# eagle.net
KiCad netlist of a schematic drawn in EAGLE
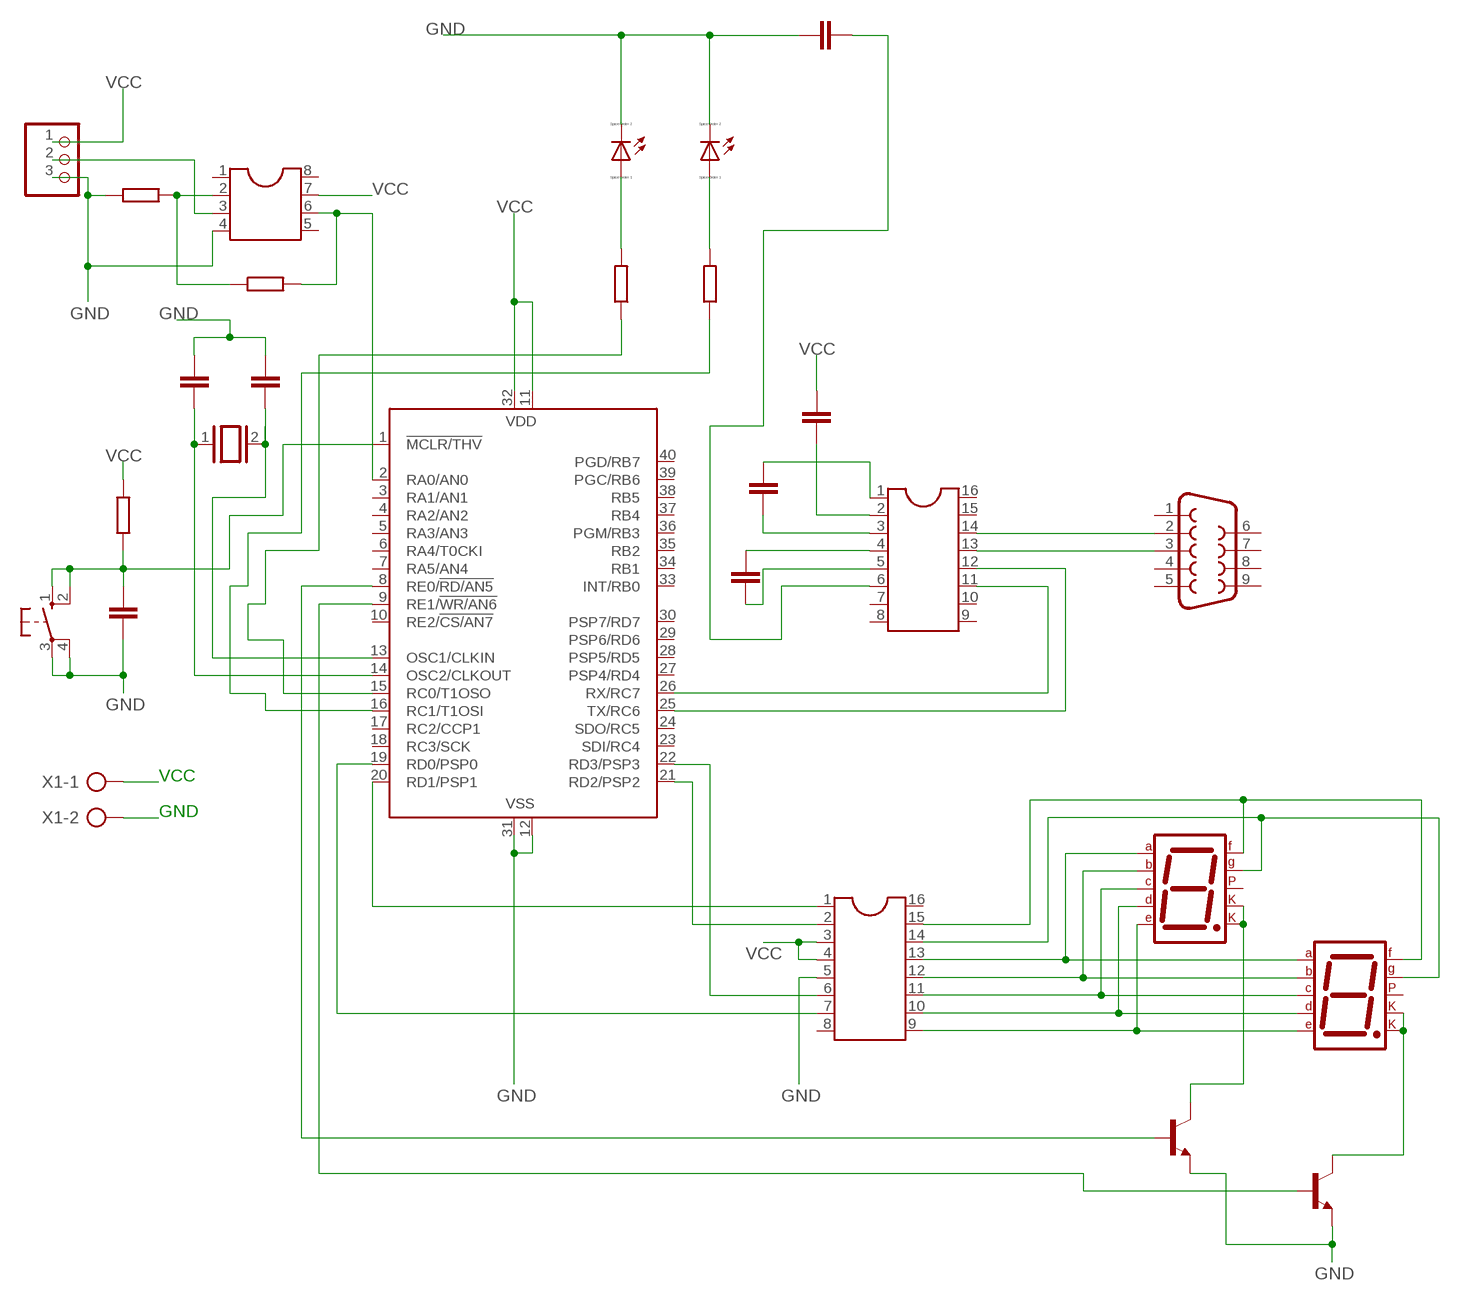
[diagram p0: schematic, sheet 1]

(export (version "E")
  (design (tool "Eeschema 10.0.6"))
  (components
    (comp (ref "4511")
      (value "DIL16")
      (footprint "eagle-import:DIL16")
      (libsource (lib "eagle-import") (part "DIL16"))
    )
    (comp (ref "AMPLIOP")
      (value "DIL8")
      (footprint "eagle-import:DIL08")
      (libsource (lib "eagle-import") (part "DIL8"))
    )
    (comp (ref "C1")
      (value "15pF")
      (footprint "eagle-import:C025-050X050")
      (libsource (lib "eagle-import") (part "C-EU025-050X050"))
    )
    (comp (ref "C2")
      (value "15pF")
      (footprint "eagle-import:C025-050X050")
      (libsource (lib "eagle-import") (part "C-EU025-050X050"))
    )
    (comp (ref "C3")
      (value "1uF")
      (footprint "eagle-import:C025-050X050")
      (libsource (lib "eagle-import") (part "C-EU025-050X050"))
    )
    (comp (ref "C4")
      (value "10uF")
      (footprint "eagle-import:C025-050X050")
      (libsource (lib "eagle-import") (part "C-EU025-050X050"))
    )
    (comp (ref "C5")
      (value "10uF")
      (footprint "eagle-import:C025-050X050")
      (libsource (lib "eagle-import") (part "C-EU025-050X050"))
    )
    (comp (ref "C7")
      (value "100u")
      (footprint "eagle-import:C025-050X050")
      (libsource (lib "eagle-import") (part "C-EU025-050X050"))
    )
    (comp (ref "C61")
      (value "10uF")
      (footprint "eagle-import:C025-050X050")
      (libsource (lib "eagle-import") (part "C-EU025-050X050"))
    )
    (comp (ref "D1")
      (value "7SEG-CK")
      (footprint "eagle-import:7SEG-13")
      (libsource (lib "eagle-import") (part "7SEG-CK"))
    )
    (comp (ref "D2")
      (value "7SEG-CK")
      (footprint "eagle-import:7SEG-13")
      (libsource (lib "eagle-import") (part "7SEG-CK"))
    )
    (comp (ref "LED1")
      (value "LED_ELD260")
      (footprint "eagle-import:LED_LD260")
      (libsource (lib "eagle-import") (part "LED_ELD260"))
    )
    (comp (ref "LED2")
      (value "LED_ELD260")
      (footprint "eagle-import:LED_LD260")
      (libsource (lib "eagle-import") (part "LED_ELD260"))
    )
    (comp (ref "LM35")
      (value "PINHD-1X3")
      (footprint "eagle-import:1X03")
      (libsource (lib "eagle-import") (part "PINHD-1X3"))
    )
    (comp (ref "MAX232")
      (value "DIL16")
      (footprint "eagle-import:DIL16")
      (libsource (lib "eagle-import") (part "DIL16"))
    )
    (comp (ref "P1/COMPIM")
      (value "F09V")
      (footprint "eagle-import:F09V")
      (libsource (lib "eagle-import") (part "F09V"))
    )
    (comp (ref "Q1")
      (value "2N2222")
      (footprint "eagle-import:TO18")
      (libsource (lib "eagle-import") (part "2N2222"))
    )
    (comp (ref "Q2")
      (value "2N2222")
      (footprint "eagle-import:TO18")
      (libsource (lib "eagle-import") (part "2N2222"))
    )
    (comp (ref "R1")
      (value "10k")
      (footprint "eagle-import:0204_7")
      (libsource (lib "eagle-import") (part "R-EU_0204/7"))
    )
    (comp (ref "R2")
      (value "100")
      (footprint "eagle-import:0204_7")
      (libsource (lib "eagle-import") (part "R-EU_0204/7"))
    )
    (comp (ref "R3")
      (value "1k")
      (footprint "eagle-import:0204_7")
      (libsource (lib "eagle-import") (part "R-EU_0204/7"))
    )
    (comp (ref "R4")
      (value "280")
      (footprint "eagle-import:0204_7")
      (libsource (lib "eagle-import") (part "R-EU_0204/7"))
    )
    (comp (ref "R5")
      (value "280")
      (footprint "eagle-import:0204_7")
      (libsource (lib "eagle-import") (part "R-EU_0204/7"))
    )
    (comp (ref "S1")
      (value "10-XX")
      (footprint "eagle-import:B3F-10XX")
      (fields (field (name "MPN") "B3F-1000"))
      (libsource (lib "eagle-import") (part "10-XX"))
    )
    (comp (ref "U1")
      (value "PIC16F877P")
      (footprint "eagle-import:DIL40")
      (fields (field (name "MF") "MICROCHIP") (field (name "MPN") "PIC16F877-04/P"))
      (libsource (lib "eagle-import") (part "PIC16F87P7"))
    )
    (comp (ref "X1")
      (value "AK300/2")
      (footprint "eagle-import:AK300_2")
      (libsource (lib "eagle-import") (part "AK300/2"))
    )
    (comp (ref "X11")
      (value "XTAL/S")
      (footprint "eagle-import:QS")
      (libsource (lib "eagle-import") (part "XTAL/S"))
    )
  )
  (nets
    (net (code "1") (name "/GND") (class "Default")
      (node (ref "4511") (pin "5") (pinfunction "5_5") (pintype "passive"))
      (node (ref "AMPLIOP") (pin "4") (pinfunction "4_4") (pintype "passive"))
      (node (ref "C1") (pin "1") (pinfunction "1_1") (pintype "passive"))
      (node (ref "C2") (pin "1") (pinfunction "1_1") (pintype "passive"))
      (node (ref "C3") (pin "1") (pinfunction "1_1") (pintype "passive"))
      (node (ref "C61") (pin "2") (pinfunction "2_2") (pintype "passive"))
      (node (ref "LED1") (pin "K") (pinfunction "C_K") (pintype "passive"))
      (node (ref "LED2") (pin "K") (pinfunction "C_K") (pintype "passive"))
      (node (ref "LM35") (pin "3") (pinfunction "3_3") (pintype "passive"))
      (node (ref "Q1") (pin "1") (pinfunction "E_1") (pintype "passive"))
      (node (ref "Q2") (pin "1") (pinfunction "E_1") (pintype "passive"))
      (node (ref "R2") (pin "1") (pinfunction "1_1") (pintype "passive"))
      (node (ref "S1") (pin "3") (pinfunction "P_3") (pintype "passive"))
      (node (ref "S1") (pin "4") (pinfunction "P1_4") (pintype "passive"))
      (node (ref "U1") (pin "12") (pinfunction "VSS_12") (pintype "power_in"))
      (node (ref "U1") (pin "31") (pinfunction "VSS_31") (pintype "power_in"))
      (node (ref "X1") (pin "2") (pinfunction "KL_2") (pintype "passive"))
    )
    (net (code "2") (name "/VCC") (class "Default")
      (node (ref "4511") (pin "3") (pinfunction "3_3") (pintype "passive"))
      (node (ref "4511") (pin "4") (pinfunction "4_4") (pintype "passive"))
      (node (ref "AMPLIOP") (pin "7") (pinfunction "7_7") (pintype "passive"))
      (node (ref "C7") (pin "2") (pinfunction "2_2") (pintype "passive"))
      (node (ref "LM35") (pin "1") (pinfunction "1_1") (pintype "passive"))
      (node (ref "R1") (pin "2") (pinfunction "2_2") (pintype "passive"))
      (node (ref "U1") (pin "11") (pinfunction "VDD_11") (pintype "power_in"))
      (node (ref "U1") (pin "32") (pinfunction "VDD_32") (pintype "power_in"))
      (node (ref "X1") (pin "1") (pinfunction "KL_1") (pintype "passive"))
    )
    (net (code "3") (name "Net-(AMPLIOP-Pad2)") (class "Default")
      (node (ref "AMPLIOP") (pin "2") (pinfunction "2_2") (pintype "passive"))
      (node (ref "R2") (pin "2") (pinfunction "2_2") (pintype "passive"))
      (node (ref "R3") (pin "1") (pinfunction "1_1") (pintype "passive"))
    )
    (net (code "4") (name "Net-(AMPLIOP-Pad3)") (class "Default")
      (node (ref "AMPLIOP") (pin "3") (pinfunction "3_3") (pintype "passive"))
      (node (ref "LM35") (pin "2") (pinfunction "2_2") (pintype "passive"))
    )
    (net (code "5") (name "Net-(C4-Pad1)") (class "Default")
      (node (ref "C4") (pin "1") (pinfunction "1_1") (pintype "passive"))
      (node (ref "MAX232") (pin "3") (pinfunction "3_3") (pintype "passive"))
    )
    (net (code "6") (name "Net-(C4-Pad2)") (class "Default")
      (node (ref "C4") (pin "2") (pinfunction "2_2") (pintype "passive"))
      (node (ref "MAX232") (pin "1") (pinfunction "1_1") (pintype "passive"))
    )
    (net (code "7") (name "Net-(C5-Pad1)") (class "Default")
      (node (ref "C5") (pin "1") (pinfunction "1_1") (pintype "passive"))
      (node (ref "MAX232") (pin "5") (pinfunction "5_5") (pintype "passive"))
    )
    (net (code "8") (name "Net-(C5-Pad2)") (class "Default")
      (node (ref "C5") (pin "2") (pinfunction "2_2") (pintype "passive"))
      (node (ref "MAX232") (pin "4") (pinfunction "4_4") (pintype "passive"))
    )
    (net (code "9") (name "Net-(C7-Pad1)") (class "Default")
      (node (ref "C7") (pin "1") (pinfunction "1_1") (pintype "passive"))
      (node (ref "MAX232") (pin "2") (pinfunction "2_2") (pintype "passive"))
    )
    (net (code "10") (name "Net-(C61-Pad1)") (class "Default")
      (node (ref "C61") (pin "1") (pinfunction "1_1") (pintype "passive"))
      (node (ref "MAX232") (pin "6") (pinfunction "6_6") (pintype "passive"))
    )
    (net (code "11") (name "Net-(D1-A)") (class "Default")
      (node (ref "4511") (pin "13") (pinfunction "13_13") (pintype "passive"))
      (node (ref "D1") (pin "7") (pinfunction "A_7") (pintype "passive"))
      (node (ref "D2") (pin "7") (pinfunction "A_7") (pintype "passive"))
    )
    (net (code "12") (name "Net-(D1-B)") (class "Default")
      (node (ref "4511") (pin "12") (pinfunction "12_12") (pintype "passive"))
      (node (ref "D1") (pin "6") (pinfunction "B_6") (pintype "passive"))
      (node (ref "D2") (pin "6") (pinfunction "B_6") (pintype "passive"))
    )
    (net (code "13") (name "Net-(D1-C)") (class "Default")
      (node (ref "4511") (pin "11") (pinfunction "11_11") (pintype "passive"))
      (node (ref "D1") (pin "4") (pinfunction "C_4") (pintype "passive"))
      (node (ref "D2") (pin "4") (pinfunction "C_4") (pintype "passive"))
    )
    (net (code "14") (name "Net-(D1-CK1)") (class "Default")
      (node (ref "D1") (pin "3") (pinfunction "CK1_3") (pintype "passive"))
      (node (ref "D1") (pin "8") (pinfunction "CK2_8") (pintype "passive"))
      (node (ref "Q1") (pin "3") (pinfunction "C_3") (pintype "passive"))
    )
    (net (code "15") (name "Net-(D1-D)") (class "Default")
      (node (ref "4511") (pin "10") (pinfunction "10_10") (pintype "passive"))
      (node (ref "D1") (pin "2") (pinfunction "D_2") (pintype "passive"))
      (node (ref "D2") (pin "2") (pinfunction "D_2") (pintype "passive"))
    )
    (net (code "16") (name "Net-(D1-E)") (class "Default")
      (node (ref "4511") (pin "9") (pinfunction "9_9") (pintype "passive"))
      (node (ref "D1") (pin "1") (pinfunction "E_1") (pintype "passive"))
      (node (ref "D2") (pin "1") (pinfunction "E_1") (pintype "passive"))
    )
    (net (code "17") (name "Net-(D1-F)") (class "Default")
      (node (ref "4511") (pin "15") (pinfunction "15_15") (pintype "passive"))
      (node (ref "D1") (pin "9") (pinfunction "F_9") (pintype "passive"))
      (node (ref "D2") (pin "9") (pinfunction "F_9") (pintype "passive"))
    )
    (net (code "18") (name "Net-(D1-G)") (class "Default")
      (node (ref "4511") (pin "14") (pinfunction "14_14") (pintype "passive"))
      (node (ref "D1") (pin "10") (pinfunction "G_10") (pintype "passive"))
      (node (ref "D2") (pin "10") (pinfunction "G_10") (pintype "passive"))
    )
    (net (code "19") (name "Net-(D2-CK1)") (class "Default")
      (node (ref "D2") (pin "3") (pinfunction "CK1_3") (pintype "passive"))
      (node (ref "D2") (pin "8") (pinfunction "CK2_8") (pintype "passive"))
      (node (ref "Q2") (pin "3") (pinfunction "C_3") (pintype "passive"))
    )
    (net (code "20") (name "Net-(LED1-PadA)") (class "Default")
      (node (ref "LED1") (pin "A") (pinfunction "A_A") (pintype "passive"))
      (node (ref "R4") (pin "2") (pinfunction "2_2") (pintype "passive"))
    )
    (net (code "21") (name "Net-(LED2-PadA)") (class "Default")
      (node (ref "LED2") (pin "A") (pinfunction "A_A") (pintype "passive"))
      (node (ref "R5") (pin "2") (pinfunction "2_2") (pintype "passive"))
    )
    (net (code "22") (name "Net-(MAX232-Pad13)") (class "Default")
      (node (ref "MAX232") (pin "13") (pinfunction "13_13") (pintype "passive"))
      (node (ref "P1/COMPIM") (pin "3") (pinfunction "3_3") (pintype "passive"))
    )
    (net (code "23") (name "Net-(MAX232-Pad14)") (class "Default")
      (node (ref "MAX232") (pin "14") (pinfunction "14_14") (pintype "passive"))
      (node (ref "P1/COMPIM") (pin "2") (pinfunction "2_2") (pintype "passive"))
    )
    (net (code "24") (name "Net-(Q1-B)") (class "Default")
      (node (ref "Q1") (pin "2") (pinfunction "B_2") (pintype "passive"))
      (node (ref "U1") (pin "8") (pinfunction "RE0/~{RD/AN5}_8") (pintype "bidirectional"))
    )
    (net (code "25") (name "Net-(Q2-B)") (class "Default")
      (node (ref "Q2") (pin "2") (pinfunction "B_2") (pintype "passive"))
      (node (ref "U1") (pin "9") (pinfunction "RE1/~{WR/AN6}_9") (pintype "bidirectional"))
    )
    (net (code "26") (name "Net-(S1-S)") (class "Default")
      (node (ref "C3") (pin "2") (pinfunction "2_2") (pintype "passive"))
      (node (ref "R1") (pin "1") (pinfunction "1_1") (pintype "passive"))
      (node (ref "S1") (pin "1") (pinfunction "S_1") (pintype "passive"))
      (node (ref "S1") (pin "2") (pinfunction "S1_2") (pintype "passive"))
      (node (ref "U1") (pin "1") (pinfunction "~{MCLR/THV}_1") (pintype "input"))
    )
    (net (code "27") (name "Net-(U1-OSC1{slash}CLKIN)") (class "Default")
      (node (ref "C1") (pin "2") (pinfunction "2_2") (pintype "passive"))
      (node (ref "U1") (pin "13") (pinfunction "OSC1/CLKIN_13") (pintype "input"))
      (node (ref "X11") (pin "2") (pinfunction "2_2") (pintype "passive"))
    )
    (net (code "28") (name "Net-(U1-OSC2{slash}CLKOUT)") (class "Default")
      (node (ref "C2") (pin "2") (pinfunction "2_2") (pintype "passive"))
      (node (ref "U1") (pin "14") (pinfunction "OSC2/CLKOUT_14") (pintype "output"))
      (node (ref "X11") (pin "1") (pinfunction "1_1") (pintype "passive"))
    )
    (net (code "29") (name "Net-(U1-RA0{slash}AN0)") (class "Default")
      (node (ref "AMPLIOP") (pin "6") (pinfunction "6_6") (pintype "passive"))
      (node (ref "R3") (pin "2") (pinfunction "2_2") (pintype "passive"))
      (node (ref "U1") (pin "2") (pinfunction "RA0/AN0_2") (pintype "bidirectional"))
    )
    (net (code "30") (name "Net-(U1-RC0{slash}T1OSO)") (class "Default")
      (node (ref "R4") (pin "1") (pinfunction "1_1") (pintype "passive"))
      (node (ref "U1") (pin "15") (pinfunction "RC0/T1OSO_15") (pintype "bidirectional"))
    )
    (net (code "31") (name "Net-(U1-RC1{slash}T1OSI)") (class "Default")
      (node (ref "R5") (pin "1") (pinfunction "1_1") (pintype "passive"))
      (node (ref "U1") (pin "16") (pinfunction "RC1/T1OSI_16") (pintype "bidirectional"))
    )
    (net (code "32") (name "Net-(U1-RD0{slash}PSP0)") (class "Default")
      (node (ref "4511") (pin "7") (pinfunction "7_7") (pintype "passive"))
      (node (ref "U1") (pin "19") (pinfunction "RD0/PSP0_19") (pintype "bidirectional"))
    )
    (net (code "33") (name "Net-(U1-RD1{slash}PSP1)") (class "Default")
      (node (ref "4511") (pin "1") (pinfunction "1_1") (pintype "passive"))
      (node (ref "U1") (pin "20") (pinfunction "RD1/PSP1_20") (pintype "bidirectional"))
    )
    (net (code "34") (name "Net-(U1-RD2{slash}PSP2)") (class "Default")
      (node (ref "4511") (pin "2") (pinfunction "2_2") (pintype "passive"))
      (node (ref "U1") (pin "21") (pinfunction "RD2/PSP2_21") (pintype "bidirectional"))
    )
    (net (code "35") (name "Net-(U1-RD3{slash}PSP3)") (class "Default")
      (node (ref "4511") (pin "6") (pinfunction "6_6") (pintype "passive"))
      (node (ref "U1") (pin "22") (pinfunction "RD3/PSP3_22") (pintype "bidirectional"))
    )
    (net (code "36") (name "Net-(U1-RX{slash}RC7)") (class "Default")
      (node (ref "MAX232") (pin "11") (pinfunction "11_11") (pintype "passive"))
      (node (ref "U1") (pin "26") (pinfunction "RX/RC7_26") (pintype "bidirectional"))
    )
    (net (code "37") (name "Net-(U1-TX{slash}RC6)") (class "Default")
      (node (ref "MAX232") (pin "12") (pinfunction "12_12") (pintype "passive"))
      (node (ref "U1") (pin "25") (pinfunction "TX/RC6_25") (pintype "bidirectional"))
    )
    (net (code "38") (name "unconnected-(4511-Pad8)") (class "Default")
      (node (ref "4511") (pin "8") (pinfunction "8_8") (pintype "passive"))
    )
    (net (code "39") (name "unconnected-(4511-Pad16)") (class "Default")
      (node (ref "4511") (pin "16") (pinfunction "16_16") (pintype "passive"))
    )
    (net (code "40") (name "unconnected-(AMPLIOP-Pad1)") (class "Default")
      (node (ref "AMPLIOP") (pin "1") (pinfunction "1_1") (pintype "passive"))
    )
    (net (code "41") (name "unconnected-(AMPLIOP-Pad5)") (class "Default")
      (node (ref "AMPLIOP") (pin "5") (pinfunction "5_5") (pintype "passive"))
    )
    (net (code "42") (name "unconnected-(AMPLIOP-Pad8)") (class "Default")
      (node (ref "AMPLIOP") (pin "8") (pinfunction "8_8") (pintype "passive"))
    )
    (net (code "43") (name "unconnected-(D1-DP-Pad5)") (class "Default")
      (node (ref "D1") (pin "5") (pinfunction "DP_5") (pintype "passive"))
    )
    (net (code "44") (name "unconnected-(D2-DP-Pad5)") (class "Default")
      (node (ref "D2") (pin "5") (pinfunction "DP_5") (pintype "passive"))
    )
    (net (code "45") (name "unconnected-(MAX232-Pad7)") (class "Default")
      (node (ref "MAX232") (pin "7") (pinfunction "7_7") (pintype "passive"))
    )
    (net (code "46") (name "unconnected-(MAX232-Pad8)") (class "Default")
      (node (ref "MAX232") (pin "8") (pinfunction "8_8") (pintype "passive"))
    )
    (net (code "47") (name "unconnected-(MAX232-Pad9)") (class "Default")
      (node (ref "MAX232") (pin "9") (pinfunction "9_9") (pintype "passive"))
    )
    (net (code "48") (name "unconnected-(MAX232-Pad10)") (class "Default")
      (node (ref "MAX232") (pin "10") (pinfunction "10_10") (pintype "passive"))
    )
    (net (code "49") (name "unconnected-(MAX232-Pad15)") (class "Default")
      (node (ref "MAX232") (pin "15") (pinfunction "15_15") (pintype "passive"))
    )
    (net (code "50") (name "unconnected-(MAX232-Pad16)") (class "Default")
      (node (ref "MAX232") (pin "16") (pinfunction "16_16") (pintype "passive"))
    )
    (net (code "51") (name "unconnected-(P1/COMPIM-Pad1)") (class "Default")
      (node (ref "P1/COMPIM") (pin "1") (pinfunction "1_1") (pintype "passive"))
    )
    (net (code "52") (name "unconnected-(P1/COMPIM-Pad4)") (class "Default")
      (node (ref "P1/COMPIM") (pin "4") (pinfunction "4_4") (pintype "passive"))
    )
    (net (code "53") (name "unconnected-(P1/COMPIM-Pad5)") (class "Default")
      (node (ref "P1/COMPIM") (pin "5") (pinfunction "5_5") (pintype "passive"))
    )
    (net (code "54") (name "unconnected-(P1/COMPIM-Pad6)") (class "Default")
      (node (ref "P1/COMPIM") (pin "6") (pinfunction "6_6") (pintype "passive"))
    )
    (net (code "55") (name "unconnected-(P1/COMPIM-Pad7)") (class "Default")
      (node (ref "P1/COMPIM") (pin "7") (pinfunction "7_7") (pintype "passive"))
    )
    (net (code "56") (name "unconnected-(P1/COMPIM-Pad8)") (class "Default")
      (node (ref "P1/COMPIM") (pin "8") (pinfunction "8_8") (pintype "passive"))
    )
    (net (code "57") (name "unconnected-(P1/COMPIM-Pad9)") (class "Default")
      (node (ref "P1/COMPIM") (pin "9") (pinfunction "9_9") (pintype "passive"))
    )
    (net (code "58") (name "unconnected-(U1-INT{slash}RB0-Pad33)") (class "Default")
      (node (ref "U1") (pin "33") (pinfunction "INT/RB0_33") (pintype "bidirectional"))
    )
    (net (code "59") (name "unconnected-(U1-PGC{slash}RB6-Pad39)") (class "Default")
      (node (ref "U1") (pin "39") (pinfunction "PGC/RB6_39") (pintype "bidirectional"))
    )
    (net (code "60") (name "unconnected-(U1-PGD{slash}RB7-Pad40)") (class "Default")
      (node (ref "U1") (pin "40") (pinfunction "PGD/RB7_40") (pintype "bidirectional"))
    )
    (net (code "61") (name "unconnected-(U1-PGM{slash}RB3-Pad36)") (class "Default")
      (node (ref "U1") (pin "36") (pinfunction "PGM/RB3_36") (pintype "bidirectional"))
    )
    (net (code "62") (name "unconnected-(U1-PSP4{slash}RD4-Pad27)") (class "Default")
      (node (ref "U1") (pin "27") (pinfunction "PSP4/RD4_27") (pintype "bidirectional"))
    )
    (net (code "63") (name "unconnected-(U1-PSP5{slash}RD5-Pad28)") (class "Default")
      (node (ref "U1") (pin "28") (pinfunction "PSP5/RD5_28") (pintype "bidirectional"))
    )
    (net (code "64") (name "unconnected-(U1-PSP6{slash}RD6-Pad29)") (class "Default")
      (node (ref "U1") (pin "29") (pinfunction "PSP6/RD6_29") (pintype "bidirectional"))
    )
    (net (code "65") (name "unconnected-(U1-PSP7{slash}RD7-Pad30)") (class "Default")
      (node (ref "U1") (pin "30") (pinfunction "PSP7/RD7_30") (pintype "bidirectional"))
    )
    (net (code "66") (name "unconnected-(U1-RA1{slash}AN1-Pad3)") (class "Default")
      (node (ref "U1") (pin "3") (pinfunction "RA1/AN1_3") (pintype "bidirectional"))
    )
    (net (code "67") (name "unconnected-(U1-RA2{slash}AN2-Pad4)") (class "Default")
      (node (ref "U1") (pin "4") (pinfunction "RA2/AN2_4") (pintype "bidirectional"))
    )
    (net (code "68") (name "unconnected-(U1-RA3{slash}AN3-Pad5)") (class "Default")
      (node (ref "U1") (pin "5") (pinfunction "RA3/AN3_5") (pintype "bidirectional"))
    )
    (net (code "69") (name "unconnected-(U1-RA4{slash}T0CKI-Pad6)") (class "Default")
      (node (ref "U1") (pin "6") (pinfunction "RA4/T0CKI_6") (pintype "bidirectional"))
    )
    (net (code "70") (name "unconnected-(U1-RA5{slash}AN4-Pad7)") (class "Default")
      (node (ref "U1") (pin "7") (pinfunction "RA5/AN4_7") (pintype "bidirectional"))
    )
    (net (code "71") (name "unconnected-(U1-RB1-Pad34)") (class "Default")
      (node (ref "U1") (pin "34") (pinfunction "RB1_34") (pintype "bidirectional"))
    )
    (net (code "72") (name "unconnected-(U1-RB2-Pad35)") (class "Default")
      (node (ref "U1") (pin "35") (pinfunction "RB2_35") (pintype "bidirectional"))
    )
    (net (code "73") (name "unconnected-(U1-RB4-Pad37)") (class "Default")
      (node (ref "U1") (pin "37") (pinfunction "RB4_37") (pintype "bidirectional"))
    )
    (net (code "74") (name "unconnected-(U1-RB5-Pad38)") (class "Default")
      (node (ref "U1") (pin "38") (pinfunction "RB5_38") (pintype "bidirectional"))
    )
    (net (code "75") (name "unconnected-(U1-RC2{slash}CCP1-Pad17)") (class "Default")
      (node (ref "U1") (pin "17") (pinfunction "RC2/CCP1_17") (pintype "bidirectional"))
    )
    (net (code "76") (name "unconnected-(U1-RC3{slash}SCK-Pad18)") (class "Default")
      (node (ref "U1") (pin "18") (pinfunction "RC3/SCK_18") (pintype "bidirectional"))
    )
    (net (code "77") (name "unconnected-(U1-RE2{slash}~{CS{slash}AN7}-Pad10)") (class "Default")
      (node (ref "U1") (pin "10") (pinfunction "RE2/~{CS/AN7}_10") (pintype "bidirectional"))
    )
    (net (code "78") (name "unconnected-(U1-SDI{slash}RC4-Pad23)") (class "Default")
      (node (ref "U1") (pin "23") (pinfunction "SDI/RC4_23") (pintype "bidirectional"))
    )
    (net (code "79") (name "unconnected-(U1-SDO{slash}RC5-Pad24)") (class "Default")
      (node (ref "U1") (pin "24") (pinfunction "SDO/RC5_24") (pintype "bidirectional"))
    )
  )
)
